# Birthday_Card.net
KiCad netlist of a schematic drawn in EAGLE
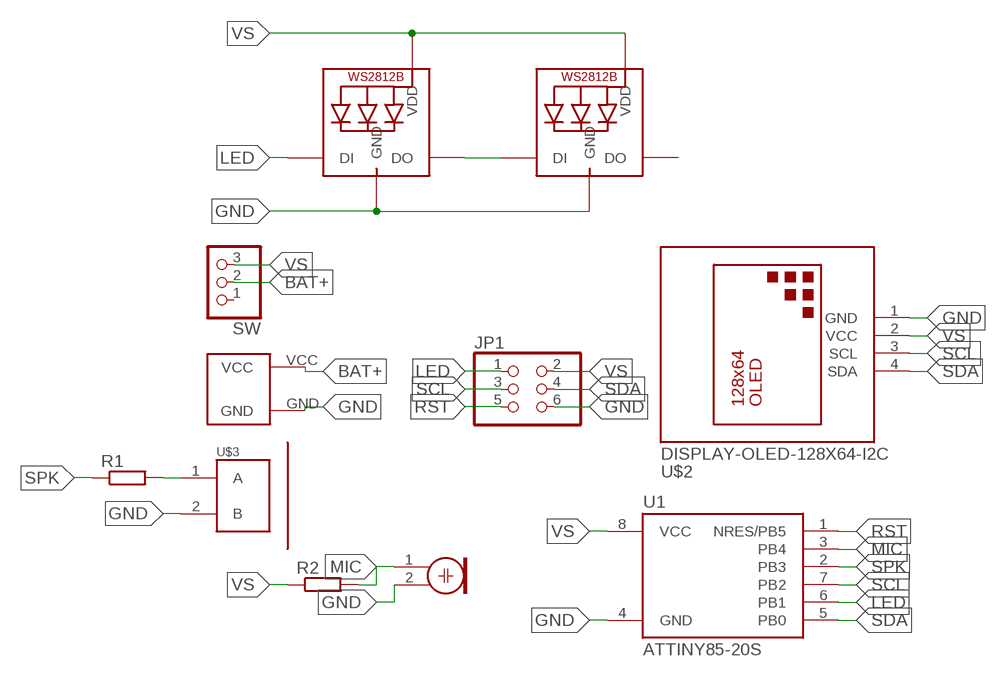
[diagram p0: schematic, sheet 1]

(export (version "E")
  (design (tool "Eeschema 10.0.6"))
  (components
    (comp (ref "JP1")
      (value "PINHD-2X3")
      (footprint "eagle-import:2X03")
      (libsource (lib "eagle-import") (part "PINHD-2X3"))
    )
    (comp (ref "LED1")
      (value "WS2812B5050")
      (footprint "eagle-import:WS2812B")
      (libsource (lib "eagle-import") (part "WS2812B5050"))
    )
    (comp (ref "LED2")
      (value "WS2812B5050")
      (footprint "eagle-import:WS2812B")
      (libsource (lib "eagle-import") (part "WS2812B5050"))
    )
    (comp (ref "M1")
      (value "ELECTRET_MICROPHON-F6050AP")
      (footprint "eagle-import:F6050AP")
      (libsource (lib "eagle-import") (part "ELECTRET_MICROPHON-F6050AP"))
    )
    (comp (ref "R1")
      (value "R-EU_R1206")
      (footprint "eagle-import:R1206")
      (libsource (lib "eagle-import") (part "R-EU_R1206"))
    )
    (comp (ref "R2")
      (value "R-EU_R1206")
      (footprint "eagle-import:R1206")
      (libsource (lib "eagle-import") (part "R-EU_R1206"))
    )
    (comp (ref "SW")
      (value "PINHD-1X3")
      (footprint "eagle-import:1X03")
      (libsource (lib "eagle-import") (part "PINHD-1X3"))
    )
    (comp (ref "U$1")
      (value "CR2032")
      (footprint "eagle-import:CR2032-20MM")
      (libsource (lib "eagle-import") (part "CR2032"))
    )
    (comp (ref "U$2")
      (value "DISPLAY-OLED-128X64-I2C")
      (footprint "eagle-import:DISPLAY-OLED-128X64-I2C")
      (libsource (lib "eagle-import") (part "DISPLAY-OLED-128X64-I2C"))
    )
    (comp (ref "U$3")
      (value "PKLCS1212E2400-R1")
      (footprint "eagle-import:BUZZ_PIEZO_SMD")
      (libsource (lib "eagle-import") (part "PKLCS1212E2400-R1"))
    )
    (comp (ref "U1")
      (value "ATTINY85-20S")
      (footprint "eagle-import:SOIC8_EIAJ_208MIL")
      (libsource (lib "eagle-import") (part "ATTINY85S-20"))
    )
  )
  (nets
    (net (code "1") (name "BAT+") (class "Default")
      (node (ref "SW") (pin "2") (pinfunction "2_2") (pintype "passive"))
      (node (ref "U$1") (pin "VCC") (pinfunction "VCC_VCC") (pintype "bidirectional"))
    )
    (net (code "2") (name "GND") (class "Default")
      (node (ref "JP1") (pin "6") (pinfunction "6_6") (pintype "passive"))
      (node (ref "LED1") (pin "3-GND") (pinfunction "GND_3-GND") (pintype "power_in"))
      (node (ref "LED2") (pin "3-GND") (pinfunction "GND_3-GND") (pintype "power_in"))
      (node (ref "M1") (pin "2") (pinfunction "2_2") (pintype "passive"))
      (node (ref "U$1") (pin "GND") (pinfunction "GND_GND") (pintype "bidirectional"))
      (node (ref "U$2") (pin "1") (pinfunction "GND_1") (pintype "power_in"))
      (node (ref "U$3") (pin "2") (pinfunction "B_2") (pintype "bidirectional"))
      (node (ref "U1") (pin "4") (pinfunction "GND_4") (pintype "power_in"))
    )
    (net (code "3") (name "LED") (class "Default")
      (node (ref "JP1") (pin "1") (pinfunction "1_1") (pintype "passive"))
      (node (ref "LED1") (pin "4-DIN") (pinfunction "DI_4-DIN") (pintype "input"))
      (node (ref "U1") (pin "6") (pinfunction "PB1_6") (pintype "bidirectional"))
    )
    (net (code "4") (name "MIC") (class "Default")
      (node (ref "M1") (pin "1") (pinfunction "1_1") (pintype "passive"))
      (node (ref "R2") (pin "2") (pinfunction "2_2") (pintype "passive"))
      (node (ref "U1") (pin "3") (pinfunction "PB4_3") (pintype "bidirectional"))
    )
    (net (code "5") (name "Net-(LED1-DO)") (class "Default")
      (node (ref "LED1") (pin "2-DOUT") (pinfunction "DO_2-DOUT") (pintype "output"))
      (node (ref "LED2") (pin "4-DIN") (pinfunction "DI_4-DIN") (pintype "input"))
    )
    (net (code "6") (name "Net-(U$3-A)") (class "Default")
      (node (ref "R1") (pin "2") (pinfunction "2_2") (pintype "passive"))
      (node (ref "U$3") (pin "1") (pinfunction "A_1") (pintype "bidirectional"))
    )
    (net (code "7") (name "RST") (class "Default")
      (node (ref "JP1") (pin "5") (pinfunction "5_5") (pintype "passive"))
      (node (ref "U1") (pin "1") (pinfunction "NRES/PB5_1") (pintype "bidirectional"))
    )
    (net (code "8") (name "SCL") (class "Default")
      (node (ref "JP1") (pin "3") (pinfunction "3_3") (pintype "passive"))
      (node (ref "U$2") (pin "3") (pinfunction "SCL_3") (pintype "bidirectional"))
      (node (ref "U1") (pin "7") (pinfunction "PB2_7") (pintype "bidirectional"))
    )
    (net (code "9") (name "SDA") (class "Default")
      (node (ref "JP1") (pin "4") (pinfunction "4_4") (pintype "passive"))
      (node (ref "U$2") (pin "4") (pinfunction "SDA_4") (pintype "bidirectional"))
      (node (ref "U1") (pin "5") (pinfunction "PB0_5") (pintype "bidirectional"))
    )
    (net (code "10") (name "SPK") (class "Default")
      (node (ref "R1") (pin "1") (pinfunction "1_1") (pintype "passive"))
      (node (ref "U1") (pin "2") (pinfunction "PB3_2") (pintype "bidirectional"))
    )
    (net (code "11") (name "VS") (class "Default")
      (node (ref "JP1") (pin "2") (pinfunction "2_2") (pintype "passive"))
      (node (ref "LED1") (pin "1-VDD") (pinfunction "VDD_1-VDD") (pintype "power_in"))
      (node (ref "LED2") (pin "1-VDD") (pinfunction "VDD_1-VDD") (pintype "power_in"))
      (node (ref "R2") (pin "1") (pinfunction "1_1") (pintype "passive"))
      (node (ref "SW") (pin "3") (pinfunction "3_3") (pintype "passive"))
      (node (ref "U$2") (pin "2") (pinfunction "VCC_2") (pintype "power_in"))
      (node (ref "U1") (pin "8") (pinfunction "VCC_8") (pintype "power_in"))
    )
    (net (code "12") (name "unconnected-(LED2-DO-Pad2-DOUT)") (class "Default")
      (node (ref "LED2") (pin "2-DOUT") (pinfunction "DO_2-DOUT") (pintype "output"))
    )
    (net (code "13") (name "unconnected-(SW-Pad1)") (class "Default")
      (node (ref "SW") (pin "1") (pinfunction "1_1") (pintype "passive"))
    )
  )
)
